# ADC.net
KiCad netlist of a schematic drawn in Altium Designer
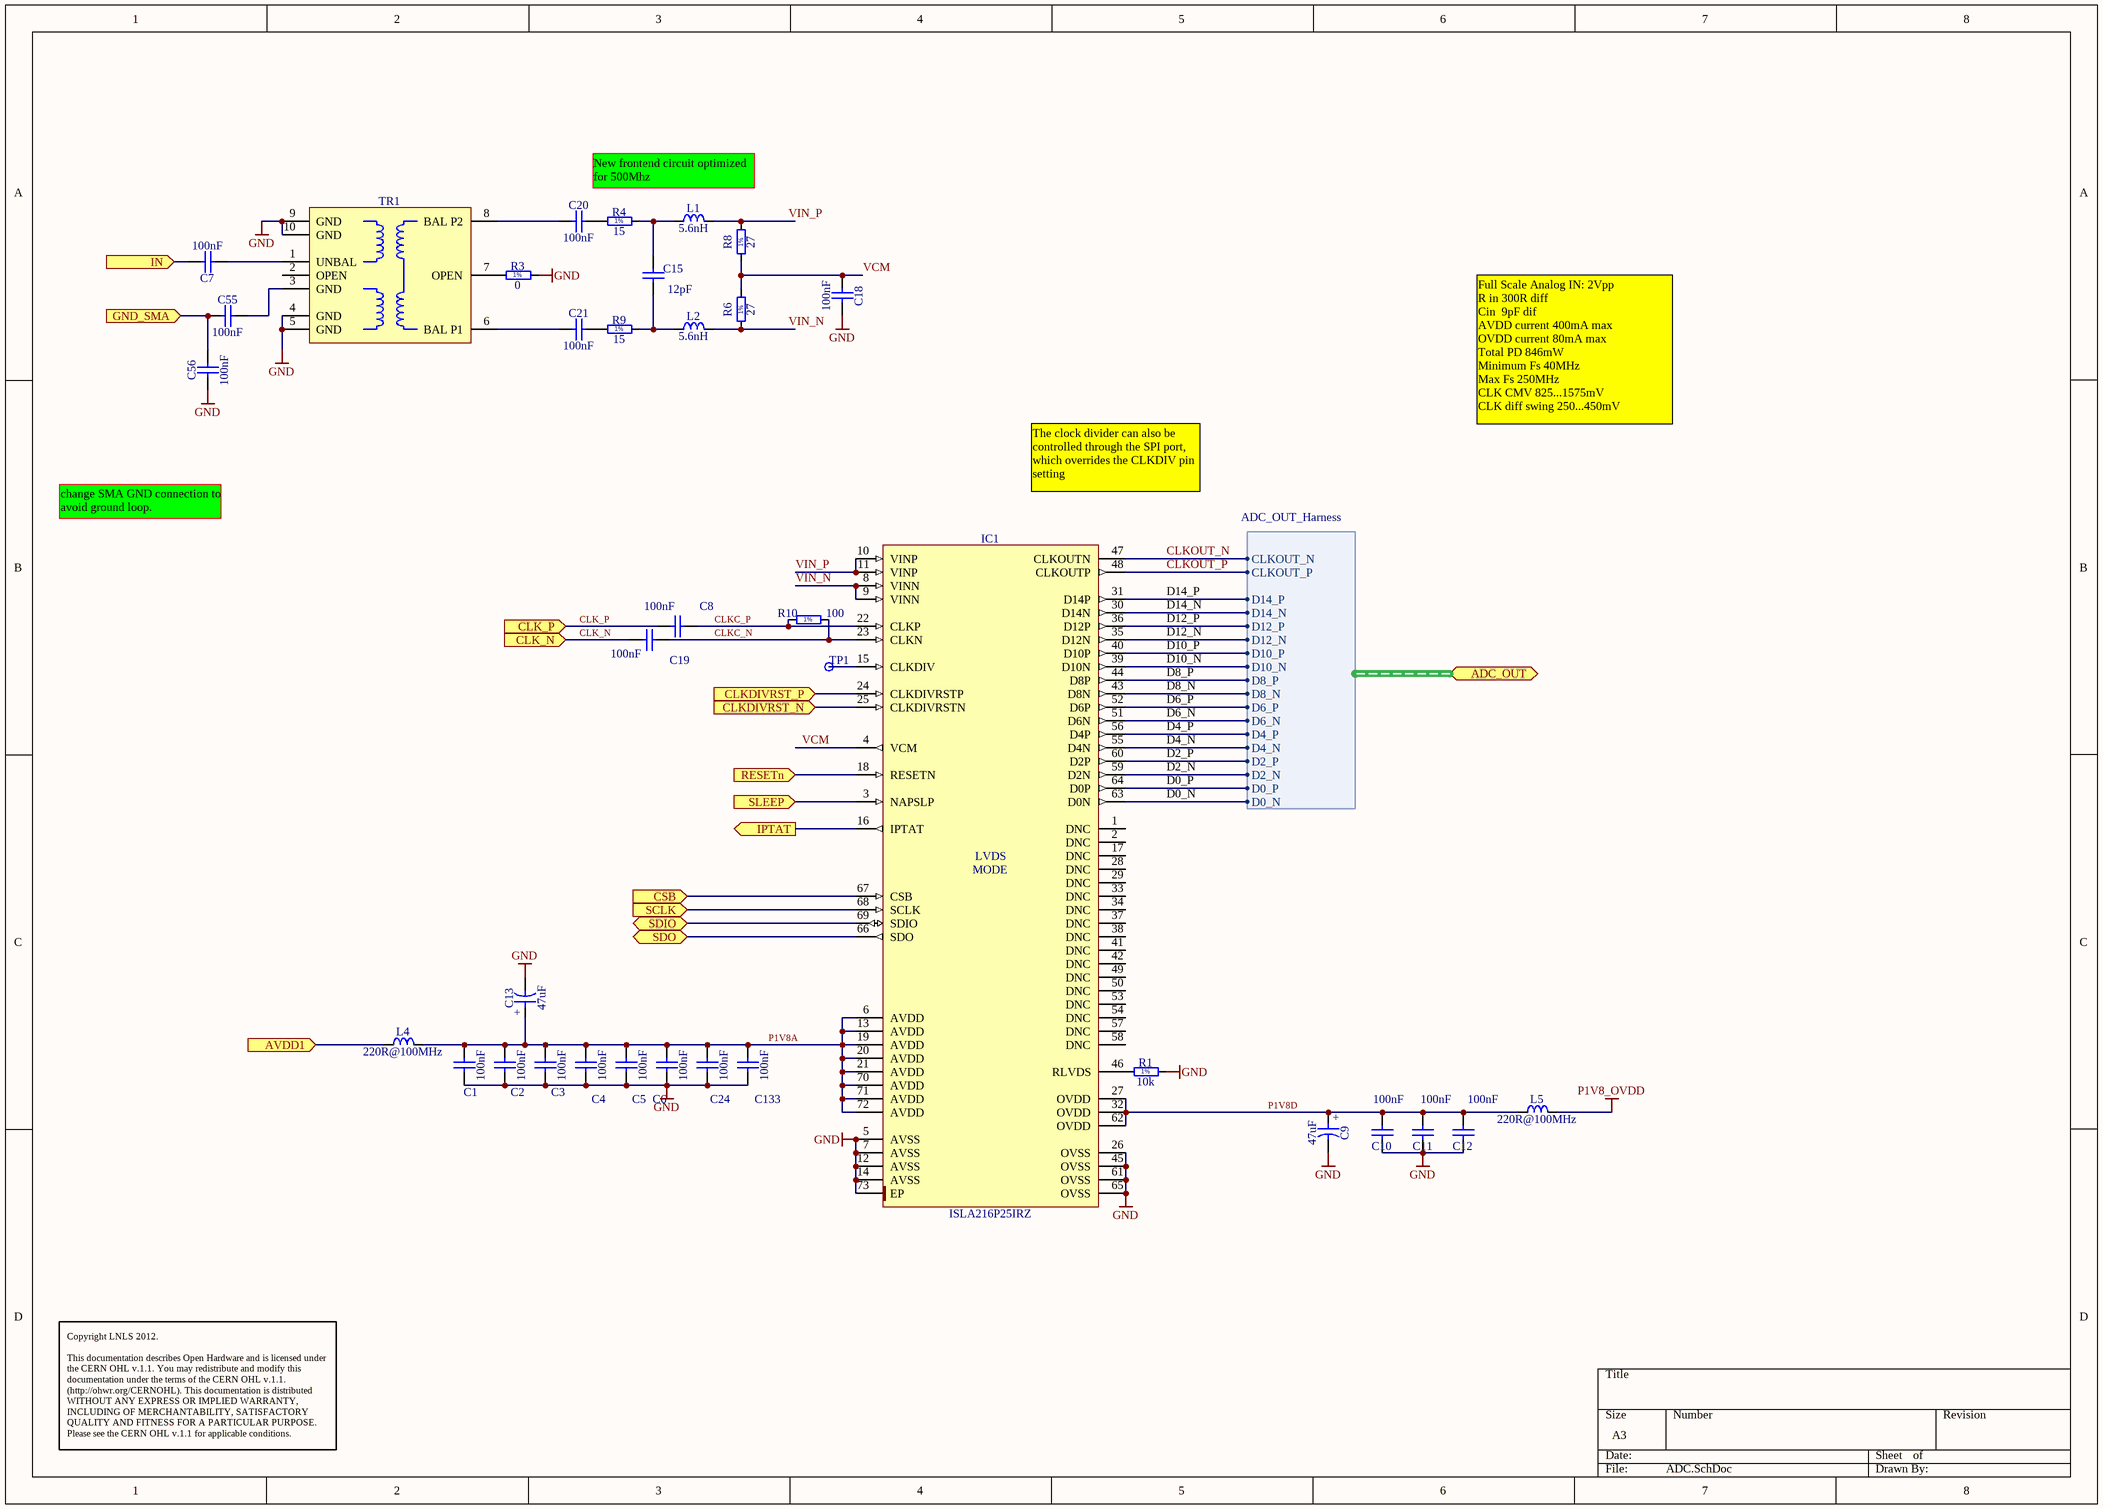
[diagram p0: ADC.SchDoc]

(export (version "E")
  (design (tool "Eeschema 10.0.6"))
  (components
    (comp (ref "C1")
      (value "100nF")
      (footprint "CAPC0603X33N")
      (description "Non-polarised capacitor")
      (fields
        (field (name "PART NUMBER") "CC0201_100NF_6.3V_10%_X5R")
        (field (name "VOLTAGE") "6.3V")
        (field (name "AUTHOR") "CERN DEM JLC")
      )
      (libsource (lib "Capacitors") (part "Capacitor - non polarized"))
    )
    (comp (ref "C2")
      (value "100nF")
      (footprint "CAPC0603X33N")
      (description "Non-polarised capacitor")
      (fields
        (field (name "PART NUMBER") "CC0201_100NF_6.3V_10%_X5R")
        (field (name "VOLTAGE") "6.3V")
        (field (name "AUTHOR") "CERN DEM JLC")
      )
      (libsource (lib "Capacitors") (part "Capacitor - non polarized"))
    )
    (comp (ref "C3")
      (value "100nF")
      (footprint "CAPC0603X33N")
      (description "Non-polarised capacitor")
      (fields
        (field (name "PART NUMBER") "CC0201_100NF_6.3V_10%_X5R")
        (field (name "VOLTAGE") "6.3V")
        (field (name "AUTHOR") "CERN DEM JLC")
      )
      (libsource (lib "Capacitors") (part "Capacitor - non polarized"))
    )
    (comp (ref "C4")
      (value "100nF")
      (footprint "CAPC0603X33N")
      (description "Non-polarised capacitor")
      (fields
        (field (name "PART NUMBER") "CC0201_100NF_6.3V_10%_X5R")
        (field (name "VOLTAGE") "6.3V")
        (field (name "AUTHOR") "CERN DEM JLC")
      )
      (libsource (lib "Capacitors") (part "Capacitor - non polarized"))
    )
    (comp (ref "C5")
      (value "100nF")
      (footprint "CAPC0603X33N")
      (description "Non-polarised capacitor")
      (fields
        (field (name "PART NUMBER") "CC0201_100NF_6.3V_10%_X5R")
        (field (name "VOLTAGE") "6.3V")
        (field (name "AUTHOR") "CERN DEM JLC")
      )
      (libsource (lib "Capacitors") (part "Capacitor - non polarized"))
    )
    (comp (ref "C6")
      (value "100nF")
      (footprint "CAPC0603X33N")
      (description "Non-polarised capacitor")
      (fields
        (field (name "PART NUMBER") "CC0201_100NF_6.3V_10%_X5R")
        (field (name "VOLTAGE") "6.3V")
        (field (name "AUTHOR") "CERN DEM JLC")
      )
      (libsource (lib "Capacitors") (part "Capacitor - non polarized"))
    )
    (comp (ref "C7")
      (value "100nF")
      (footprint "CAPC0603X33N")
      (description "Non-polarised capacitor")
      (fields
        (field (name "PART NUMBER") "CC0201_100NF_6.3V_10%_X5R")
        (field (name "VOLTAGE") "6.3V")
        (field (name "AUTHOR") "CERN DEM JLC")
      )
      (libsource (lib "Capacitors") (part "Capacitor - non polarized"))
    )
    (comp (ref "C8")
      (value "100nF")
      (footprint "CAPC0603X33N")
      (description "Non-polarised capacitor")
      (fields
        (field (name "PART NUMBER") "CC0201_100NF_6.3V_10%_X5R")
        (field (name "VOLTAGE") "6.3V")
        (field (name "AUTHOR") "CERN DEM JLC")
      )
      (libsource (lib "Capacitors") (part "Capacitor - non polarized"))
    )
    (comp (ref "C9")
      (value "47uF")
      (footprint "CAPMP3528X210N")
      (description "Polarised capacitor")
      (fields
        (field (name "PART NUMBER") "CTE3528-21_47UF_6.3V_10%_LESR0250")
        (field (name "VOLTAGE") "6.3V")
        (field (name "AUTHOR") "CERN DEM JLC")
      )
      (libsource (lib "Capacitors") (part "Capacitor - polarized"))
    )
    (comp (ref "C10")
      (value "100nF")
      (footprint "CAPC0603X33N")
      (description "Non-polarised capacitor")
      (fields
        (field (name "PART NUMBER") "CC0201_100NF_6.3V_10%_X5R")
        (field (name "VOLTAGE") "6.3V")
        (field (name "AUTHOR") "CERN DEM JLC")
      )
      (libsource (lib "Capacitors") (part "Capacitor - non polarized"))
    )
    (comp (ref "C11")
      (value "100nF")
      (footprint "CAPC0603X33N")
      (description "Non-polarised capacitor")
      (fields
        (field (name "PART NUMBER") "CC0201_100NF_6.3V_10%_X5R")
        (field (name "VOLTAGE") "6.3V")
        (field (name "AUTHOR") "CERN DEM JLC")
      )
      (libsource (lib "Capacitors") (part "Capacitor - non polarized"))
    )
    (comp (ref "C12")
      (value "100nF")
      (footprint "CAPC0603X33N")
      (description "Non-polarised capacitor")
      (fields
        (field (name "PART NUMBER") "CC0201_100NF_6.3V_10%_X5R")
        (field (name "VOLTAGE") "6.3V")
        (field (name "AUTHOR") "CERN DEM JLC")
      )
      (libsource (lib "Capacitors") (part "Capacitor - non polarized"))
    )
    (comp (ref "C13")
      (value "47uF")
      (footprint "CAPMP3528X210N")
      (description "Polarised capacitor")
      (fields
        (field (name "PART NUMBER") "CTE3528-21_47UF_6.3V_10%_LESR0250")
        (field (name "VOLTAGE") "6.3V")
        (field (name "AUTHOR") "CERN DEM JLC")
      )
      (libsource (lib "Capacitors") (part "Capacitor - polarized"))
    )
    (comp (ref "C15")
      (value "12pF")
      (footprint "CAPC2012X135N")
      (description "Non-polarised capacitor")
      (fields
        (field (name "PART NUMBER") "CC0805_12PF_50V_5%_NP0")
        (field (name "VOLTAGE") "50V")
        (field (name "AUTHOR") "CERN DEM JLC")
      )
      (libsource (lib "Capacitors") (part "Capacitor - non polarized"))
    )
    (comp (ref "C18")
      (value "100nF")
      (footprint "CAPC0603X33N")
      (description "Non-polarised capacitor")
      (fields
        (field (name "PART NUMBER") "CC0201_100NF_6.3V_10%_X5R")
        (field (name "VOLTAGE") "6.3V")
        (field (name "AUTHOR") "CERN DEM JLC")
      )
      (libsource (lib "Capacitors") (part "Capacitor - non polarized"))
    )
    (comp (ref "C19")
      (value "100nF")
      (footprint "CAPC0603X33N")
      (description "Non-polarised capacitor")
      (fields
        (field (name "PART NUMBER") "CC0201_100NF_6.3V_10%_X5R")
        (field (name "VOLTAGE") "6.3V")
        (field (name "AUTHOR") "CERN DEM JLC")
      )
      (libsource (lib "Capacitors") (part "Capacitor - non polarized"))
    )
    (comp (ref "C20")
      (value "100nF")
      (footprint "CAPC0603X33N")
      (description "Non-polarised capacitor")
      (fields
        (field (name "PART NUMBER") "CC0201_100NF_6.3V_10%_X5R")
        (field (name "VOLTAGE") "6.3V")
        (field (name "AUTHOR") "CERN DEM JLC")
      )
      (libsource (lib "Capacitors") (part "Capacitor - non polarized"))
    )
    (comp (ref "C21")
      (value "100nF")
      (footprint "CAPC0603X33N")
      (description "Non-polarised capacitor")
      (fields
        (field (name "PART NUMBER") "CC0201_100NF_6.3V_10%_X5R")
        (field (name "VOLTAGE") "6.3V")
        (field (name "AUTHOR") "CERN DEM JLC")
      )
      (libsource (lib "Capacitors") (part "Capacitor - non polarized"))
    )
    (comp (ref "C24")
      (value "100nF")
      (footprint "CAPC0603X33N")
      (description "Non-polarised capacitor")
      (fields
        (field (name "PART NUMBER") "CC0201_100NF_6.3V_10%_X5R")
        (field (name "VOLTAGE") "6.3V")
        (field (name "AUTHOR") "CERN DEM JLC")
      )
      (libsource (lib "Capacitors") (part "Capacitor - non polarized"))
    )
    (comp (ref "C55")
      (value "100nF")
      (footprint "CAPC0603X33N")
      (description "Non-polarised capacitor")
      (fields
        (field (name "PART NUMBER") "CC0201_100NF_6.3V_10%_X5R")
        (field (name "VOLTAGE") "6.3V")
        (field (name "AUTHOR") "CERN DEM JLC")
      )
      (libsource (lib "Capacitors") (part "Capacitor - non polarized"))
    )
    (comp (ref "C56")
      (value "100nF")
      (footprint "CAPC0603X33N")
      (description "Non-polarised capacitor")
      (fields
        (field (name "PART NUMBER") "CC0201_100NF_6.3V_10%_X5R")
        (field (name "VOLTAGE") "6.3V")
        (field (name "AUTHOR") "CERN DEM JLC")
      )
      (libsource (lib "Capacitors") (part "Capacitor - non polarized"))
    )
    (comp (ref "C133")
      (value "100nF")
      (footprint "CAPC0603X33N")
      (description "Non-polarised capacitor")
      (fields
        (field (name "PART NUMBER") "CC0201_100NF_6.3V_10%_X5R")
        (field (name "VOLTAGE") "6.3V")
        (field (name "AUTHOR") "CERN DEM JLC")
      )
      (libsource (lib "Capacitors") (part "Capacitor - non polarized"))
    )
    (comp (ref "IC1")
      (value "ISLA216P25IRZ")
      (footprint "INTERSIL_L72.10x10E")
      (description "16-Bit, 250MSPS ADC (LVDS Mode)")
      (fields (field (name "MANUFACTURER") "INTERSIL") (field (name "AUTHOR") "CERN DEM JLC"))
      (libsource (lib "ICs And Semiconductors") (part "ISLA216P25IRZ_LVDS"))
    )
    (comp (ref "L1")
      (value "5.6nH")
      (footprint "INDC1005X55N")
      (description "Inductor")
      (fields
        (field (name "PART NUMBER") "IND0402_5.6nH_0.3n_JOHANSON_L-07C5N6SV6T")
        (field (name "POWER") "300mA")
        (field (name "AUTHOR") "LNLS DIG GBMB")
      )
      (libsource (lib "Inductors & Transformers") (part "Inductor"))
    )
    (comp (ref "L2")
      (value "5.6nH")
      (footprint "INDC1005X55N")
      (description "Inductor")
      (fields
        (field (name "PART NUMBER") "IND0402_5.6nH_0.3n_JOHANSON_L-07C5N6SV6T")
        (field (name "POWER") "300mA")
        (field (name "AUTHOR") "LNLS DIG GBMB")
      )
      (libsource (lib "Inductors & Transformers") (part "Inductor"))
    )
    (comp (ref "L4")
      (value "220R@100MHz")
      (footprint "INDC2012X105N")
      (description "Inductor")
      (fields
        (field (name "PART NUMBER") "IND0805_MURATA_BLM21PG221SN1D")
        (field (name "POWER") "2A")
        (field (name "AUTHOR") "CERN DEM JLC")
      )
      (libsource (lib "Inductors & Transformers") (part "Inductor"))
    )
    (comp (ref "L5")
      (value "220R@100MHz")
      (footprint "INDC2012X105N")
      (description "Inductor")
      (fields
        (field (name "PART NUMBER") "IND0805_MURATA_BLM21PG221SN1D")
        (field (name "POWER") "2A")
        (field (name "AUTHOR") "CERN DEM JLC")
      )
      (libsource (lib "Inductors & Transformers") (part "Inductor"))
    )
    (comp (ref "R1")
      (value "10k")
      (footprint "RESC1005X40N")
      (description "Resistor - 1%")
      (fields
        (field (name "PART NUMBER") "R0402_10K_1%_0.0625W_100PPM")
        (field (name "POWER") "0.0625W")
        (field (name "AUTHOR") "CERN DEM JLC")
      )
      (libsource (lib "Resistors") (part "Resistor - 1%"))
    )
    (comp (ref "R3")
      (value "0")
      (footprint "RESC1005X40N")
      (description "Resistor - 1%")
      (fields
        (field (name "PART NUMBER") "R0402_0R_JUMPER")
        (field (name "MANUFACTURER") "GENERIC")
        (field (name "AUTHOR") "CERN DEM JLC")
      )
      (libsource (lib "Resistors") (part "Resistor - 1%"))
    )
    (comp (ref "R4")
      (value "15")
      (footprint "RESC1005X40N")
      (description "Resistor - 1%")
      (fields
        (field (name "PART NUMBER") "CRCW04026R98FKED")
        (field (name "POWER") "0.0625W")
        (field (name "AUTHOR") "CERN DEM JLC")
      )
      (libsource (lib "Resistors") (part "Resistor - 1%"))
    )
    (comp (ref "R6")
      (value "27")
      (footprint "RESC1005X40N")
      (description "Resistor - 1%")
      (fields
        (field (name "PART NUMBER") "RC0402FR-0720RL")
        (field (name "POWER") "0.0625W")
        (field (name "AUTHOR") "CERN DEM JLC")
      )
      (libsource (lib "Resistors") (part "Resistor - 1%"))
    )
    (comp (ref "R8")
      (value "27")
      (footprint "RESC1005X40N")
      (description "Resistor - 1%")
      (fields
        (field (name "PART NUMBER") "RC0402FR-0720RL")
        (field (name "POWER") "0.0625W")
        (field (name "AUTHOR") "CERN DEM JLC")
      )
      (libsource (lib "Resistors") (part "Resistor - 1%"))
    )
    (comp (ref "R9")
      (value "15")
      (footprint "RESC1005X40N")
      (description "Resistor - 1%")
      (fields
        (field (name "PART NUMBER") "CRCW04026R98FKED")
        (field (name "POWER") "0.0625W")
        (field (name "AUTHOR") "CERN DEM JLC")
      )
      (libsource (lib "Resistors") (part "Resistor - 1%"))
    )
    (comp (ref "R10")
      (value "100")
      (footprint "RESC1005X40N")
      (description "Resistor - 1%")
      (fields
        (field (name "PART NUMBER") "R0402_100R_1%_0.0625W_100PPM")
        (field (name "POWER") "0.0625W")
        (field (name "AUTHOR") "CERN DEM JLC")
      )
      (libsource (lib "Resistors") (part "Resistor - 1%"))
    )
    (comp (ref "TP1")
      (value "~")
      (footprint "TPR120")
      (description "Test Point")
      (fields (field (name "PART NUMBER") "SMD_PAD_1.20_d_MM") (field (name "AUTHOR") "LNLS DIG GBMB"))
      (libsource (lib "Eletro-mechanical") (part "Test Point"))
    )
    (comp (ref "TR1")
      (value "~")
      (footprint "XFMR_ANAREN_BD0205F5050A00")
      (description "70MHz - 1000MHz Ultra Low Profile Sub-Miniature Balanced to Unbalanced Transformer")
      (fields
        (field (name "PART NUMBER") "XFMR_ANAREN_BD0205F5050A00")
        (field (name "MANUFACTURER") "ANAREN")
        (field (name "AUTHOR") "CERN DEM JLC")
      )
      (libsource (lib "Inductors & Transformers") (part "XFMR_ANAREN_BD0205F5050A00"))
    )
  )
  (nets
    (net (code "2") (name "/AVDD1") (class "Default")
      (node (ref "L4") (pin "1") (pinfunction "1_1") (pintype "passive"))
    )
    (net (code "3") (name "/CLKC_N") (class "Default")
      (node (ref "C19") (pin "2") (pinfunction "2_2") (pintype "passive"))
      (node (ref "IC1") (pin "23") (pinfunction "CLKN_23") (pintype "input"))
      (node (ref "R10") (pin "2") (pinfunction "2_2") (pintype "passive"))
    )
    (net (code "4") (name "/CLKC_P") (class "Default")
      (node (ref "C8") (pin "2") (pinfunction "2_2") (pintype "passive"))
      (node (ref "IC1") (pin "22") (pinfunction "CLKP_22") (pintype "input"))
      (node (ref "R10") (pin "1") (pinfunction "1_1") (pintype "passive"))
    )
    (net (code "5") (name "/CLKDIVRST_N") (class "Default")
      (node (ref "IC1") (pin "25") (pinfunction "CLKDIVRSTN_25") (pintype "input"))
    )
    (net (code "6") (name "/CLKDIVRST_P") (class "Default")
      (node (ref "IC1") (pin "24") (pinfunction "CLKDIVRSTP_24") (pintype "input"))
    )
    (net (code "7") (name "/CLKOUT_N") (class "Default")
      (node (ref "IC1") (pin "47") (pinfunction "CLKOUTN_47") (pintype "open_collector"))
    )
    (net (code "8") (name "/CLKOUT_P") (class "Default")
      (node (ref "IC1") (pin "48") (pinfunction "CLKOUTP_48") (pintype "output"))
    )
    (net (code "9") (name "/CLK_N") (class "Default")
      (node (ref "C19") (pin "1") (pinfunction "1_1") (pintype "passive"))
    )
    (net (code "10") (name "/CLK_P") (class "Default")
      (node (ref "C8") (pin "1") (pinfunction "1_1") (pintype "passive"))
    )
    (net (code "11") (name "/CSB") (class "Default")
      (node (ref "IC1") (pin "67") (pinfunction "CSB_67") (pintype "input"))
    )
    (net (code "12") (name "/D0_N") (class "Default")
      (node (ref "IC1") (pin "63") (pinfunction "D0N_63") (pintype "output"))
    )
    (net (code "13") (name "/D0_P") (class "Default")
      (node (ref "IC1") (pin "64") (pinfunction "D0P_64") (pintype "output"))
    )
    (net (code "14") (name "/D2_N") (class "Default")
      (node (ref "IC1") (pin "59") (pinfunction "D2N_59") (pintype "output"))
    )
    (net (code "15") (name "/D2_P") (class "Default")
      (node (ref "IC1") (pin "60") (pinfunction "D2P_60") (pintype "output"))
    )
    (net (code "16") (name "/D4_N") (class "Default")
      (node (ref "IC1") (pin "55") (pinfunction "D4N_55") (pintype "output"))
    )
    (net (code "17") (name "/D4_P") (class "Default")
      (node (ref "IC1") (pin "56") (pinfunction "D4P_56") (pintype "output"))
    )
    (net (code "18") (name "/D6_N") (class "Default")
      (node (ref "IC1") (pin "51") (pinfunction "D6N_51") (pintype "output"))
    )
    (net (code "19") (name "/D6_P") (class "Default")
      (node (ref "IC1") (pin "52") (pinfunction "D6P_52") (pintype "output"))
    )
    (net (code "20") (name "/D8_N") (class "Default")
      (node (ref "IC1") (pin "43") (pinfunction "D8N_43") (pintype "output"))
    )
    (net (code "21") (name "/D8_P") (class "Default")
      (node (ref "IC1") (pin "44") (pinfunction "D8P_44") (pintype "output"))
    )
    (net (code "22") (name "/D10_N") (class "Default")
      (node (ref "IC1") (pin "39") (pinfunction "D10N_39") (pintype "output"))
    )
    (net (code "23") (name "/D10_P") (class "Default")
      (node (ref "IC1") (pin "40") (pinfunction "D10P_40") (pintype "output"))
    )
    (net (code "24") (name "/D12_N") (class "Default")
      (node (ref "IC1") (pin "35") (pinfunction "D12N_35") (pintype "output"))
    )
    (net (code "25") (name "/D12_P") (class "Default")
      (node (ref "IC1") (pin "36") (pinfunction "D12P_36") (pintype "output"))
    )
    (net (code "26") (name "/D14_N") (class "Default")
      (node (ref "IC1") (pin "30") (pinfunction "D14N_30") (pintype "output"))
    )
    (net (code "27") (name "/D14_P") (class "Default")
      (node (ref "IC1") (pin "31") (pinfunction "D14P_31") (pintype "output"))
    )
    (net (code "28") (name "/GND_SMA") (class "Default")
      (node (ref "C55") (pin "1") (pinfunction "1_1") (pintype "passive"))
      (node (ref "C56") (pin "2") (pinfunction "2_2") (pintype "passive"))
    )
    (net (code "29") (name "/IN") (class "Default")
      (node (ref "C7") (pin "2") (pinfunction "2_2") (pintype "passive"))
    )
    (net (code "30") (name "/IPTAT") (class "Default")
      (node (ref "IC1") (pin "16") (pinfunction "IPTAT_16") (pintype "output"))
    )
    (net (code "31") (name "/P1V8A") (class "Default")
      (node (ref "C1") (pin "2") (pinfunction "2_2") (pintype "passive"))
      (node (ref "C13") (pin "1") (pinfunction "1_1") (pintype "passive"))
      (node (ref "C133") (pin "2") (pinfunction "2_2") (pintype "passive"))
      (node (ref "C2") (pin "2") (pinfunction "2_2") (pintype "passive"))
      (node (ref "C24") (pin "2") (pinfunction "2_2") (pintype "passive"))
      (node (ref "C3") (pin "2") (pinfunction "2_2") (pintype "passive"))
      (node (ref "C4") (pin "2") (pinfunction "2_2") (pintype "passive"))
      (node (ref "C5") (pin "2") (pinfunction "2_2") (pintype "passive"))
      (node (ref "C6") (pin "2") (pinfunction "2_2") (pintype "passive"))
      (node (ref "IC1") (pin "13") (pinfunction "AVDD_13") (pintype "power_in"))
      (node (ref "IC1") (pin "19") (pinfunction "AVDD_19") (pintype "power_in"))
      (node (ref "IC1") (pin "20") (pinfunction "AVDD_20") (pintype "power_in"))
      (node (ref "IC1") (pin "21") (pinfunction "AVDD_21") (pintype "power_in"))
      (node (ref "IC1") (pin "6") (pinfunction "AVDD_6") (pintype "power_in"))
      (node (ref "IC1") (pin "70") (pinfunction "AVDD_70") (pintype "power_in"))
      (node (ref "IC1") (pin "71") (pinfunction "AVDD_71") (pintype "power_in"))
      (node (ref "IC1") (pin "72") (pinfunction "AVDD_72") (pintype "power_in"))
      (node (ref "L4") (pin "2") (pinfunction "2_2") (pintype "passive"))
    )
    (net (code "32") (name "/P1V8D") (class "Default")
      (node (ref "C10") (pin "2") (pinfunction "2_2") (pintype "passive"))
      (node (ref "C11") (pin "2") (pinfunction "2_2") (pintype "passive"))
      (node (ref "C12") (pin "2") (pinfunction "2_2") (pintype "passive"))
      (node (ref "C9") (pin "1") (pinfunction "1_1") (pintype "passive"))
      (node (ref "IC1") (pin "27") (pinfunction "OVDD_27") (pintype "power_in"))
      (node (ref "IC1") (pin "32") (pinfunction "OVDD_32") (pintype "power_in"))
      (node (ref "IC1") (pin "62") (pinfunction "OVDD_62") (pintype "power_in"))
      (node (ref "L5") (pin "1") (pinfunction "1_1") (pintype "passive"))
    )
    (net (code "33") (name "/RESETn") (class "Default")
      (node (ref "IC1") (pin "18") (pinfunction "RESETN_18") (pintype "input"))
    )
    (net (code "34") (name "/SCLK") (class "Default")
      (node (ref "IC1") (pin "68") (pinfunction "SCLK_68") (pintype "input"))
    )
    (net (code "35") (name "/SDIO") (class "Default")
      (node (ref "IC1") (pin "69") (pinfunction "SDIO_69") (pintype "bidirectional"))
    )
    (net (code "36") (name "/SDO") (class "Default")
      (node (ref "IC1") (pin "66") (pinfunction "SDO_66") (pintype "output"))
    )
    (net (code "37") (name "/SLEEP") (class "Default")
      (node (ref "IC1") (pin "3") (pinfunction "NAPSLP_3") (pintype "input"))
    )
    (net (code "38") (name "/VCM") (class "Default")
      (node (ref "C18") (pin "1") (pinfunction "1_1") (pintype "passive"))
      (node (ref "IC1") (pin "4") (pinfunction "VCM_4") (pintype "output"))
      (node (ref "R6") (pin "2") (pinfunction "2_2") (pintype "passive"))
      (node (ref "R8") (pin "1") (pinfunction "1_1") (pintype "passive"))
    )
    (net (code "39") (name "/VIN_N") (class "Default")
      (node (ref "IC1") (pin "8") (pinfunction "VINN_8") (pintype "input"))
      (node (ref "IC1") (pin "9") (pinfunction "VINN_9") (pintype "input"))
      (node (ref "L2") (pin "2") (pinfunction "2_2") (pintype "passive"))
      (node (ref "R6") (pin "1") (pinfunction "1_1") (pintype "passive"))
    )
    (net (code "40") (name "/VIN_P") (class "Default")
      (node (ref "IC1") (pin "10") (pinfunction "VINP_10") (pintype "input"))
      (node (ref "IC1") (pin "11") (pinfunction "VINP_11") (pintype "input"))
      (node (ref "L1") (pin "2") (pinfunction "2_2") (pintype "passive"))
      (node (ref "R8") (pin "2") (pinfunction "2_2") (pintype "passive"))
    )
    (net (code "42") (name "GND") (class "Default")
      (node (ref "C1") (pin "1") (pinfunction "1_1") (pintype "passive"))
      (node (ref "C10") (pin "1") (pinfunction "1_1") (pintype "passive"))
      (node (ref "C11") (pin "1") (pinfunction "1_1") (pintype "passive"))
      (node (ref "C12") (pin "1") (pinfunction "1_1") (pintype "passive"))
      (node (ref "C13") (pin "2") (pinfunction "2_2") (pintype "passive"))
      (node (ref "C133") (pin "1") (pinfunction "1_1") (pintype "passive"))
      (node (ref "C18") (pin "2") (pinfunction "2_2") (pintype "passive"))
      (node (ref "C2") (pin "1") (pinfunction "1_1") (pintype "passive"))
      (node (ref "C24") (pin "1") (pinfunction "1_1") (pintype "passive"))
      (node (ref "C3") (pin "1") (pinfunction "1_1") (pintype "passive"))
      (node (ref "C4") (pin "1") (pinfunction "1_1") (pintype "passive"))
      (node (ref "C5") (pin "1") (pinfunction "1_1") (pintype "passive"))
      (node (ref "C56") (pin "1") (pinfunction "1_1") (pintype "passive"))
      (node (ref "C6") (pin "1") (pinfunction "1_1") (pintype "passive"))
      (node (ref "C9") (pin "2") (pinfunction "2_2") (pintype "passive"))
      (node (ref "IC1") (pin "12") (pinfunction "AVSS_12") (pintype "power_in"))
      (node (ref "IC1") (pin "14") (pinfunction "AVSS_14") (pintype "power_in"))
      (node (ref "IC1") (pin "26") (pinfunction "OVSS_26") (pintype "power_in"))
      (node (ref "IC1") (pin "45") (pinfunction "OVSS_45") (pintype "power_in"))
      (node (ref "IC1") (pin "5") (pinfunction "AVSS_5") (pintype "power_in"))
      (node (ref "IC1") (pin "61") (pinfunction "OVSS_61") (pintype "power_in"))
      (node (ref "IC1") (pin "65") (pinfunction "OVSS_65") (pintype "power_in"))
      (node (ref "IC1") (pin "7") (pinfunction "AVSS_7") (pintype "power_in"))
      (node (ref "IC1") (pin "73") (pinfunction "EP_73") (pintype "power_in"))
      (node (ref "R1") (pin "2") (pinfunction "2_2") (pintype "passive"))
      (node (ref "R3") (pin "2") (pinfunction "2_2") (pintype "passive"))
      (node (ref "TR1") (pin "10") (pinfunction "GND_10") (pintype "power_in"))
      (node (ref "TR1") (pin "4") (pinfunction "GND_4") (pintype "power_in"))
      (node (ref "TR1") (pin "5") (pinfunction "GND_5") (pintype "power_in"))
      (node (ref "TR1") (pin "9") (pinfunction "GND_9") (pintype "power_in"))
    )
    (net (code "43") (name "Net-(C15-Pad1)") (class "Default")
      (node (ref "C15") (pin "1") (pinfunction "1_1") (pintype "passive"))
      (node (ref "L2") (pin "1") (pinfunction "1_1") (pintype "passive"))
      (node (ref "R9") (pin "2") (pinfunction "2_2") (pintype "passive"))
    )
    (net (code "44") (name "Net-(C15-Pad2)") (class "Default")
      (node (ref "C15") (pin "2") (pinfunction "2_2") (pintype "passive"))
      (node (ref "L1") (pin "1") (pinfunction "1_1") (pintype "passive"))
      (node (ref "R4") (pin "2") (pinfunction "2_2") (pintype "passive"))
    )
    (net (code "45") (name "Net-(C20-Pad2)") (class "Default")
      (node (ref "C20") (pin "2") (pinfunction "2_2") (pintype "passive"))
      (node (ref "R4") (pin "1") (pinfunction "1_1") (pintype "passive"))
    )
    (net (code "46") (name "Net-(C21-Pad2)") (class "Default")
      (node (ref "C21") (pin "2") (pinfunction "2_2") (pintype "passive"))
      (node (ref "R9") (pin "1") (pinfunction "1_1") (pintype "passive"))
    )
    (net (code "47") (name "Net-(C55-Pad2)") (class "Default")
      (node (ref "C55") (pin "2") (pinfunction "2_2") (pintype "passive"))
      (node (ref "TR1") (pin "3") (pinfunction "GND_3") (pintype "power_in"))
    )
    (net (code "48") (name "Net-(IC1-CLKDIV)") (class "Default")
      (node (ref "IC1") (pin "15") (pinfunction "CLKDIV_15") (pintype "input"))
      (node (ref "TP1") (pin "1") (pinfunction "1_1") (pintype "bidirectional"))
    )
    (net (code "49") (name "Net-(IC1-RLVDS)") (class "Default")
      (node (ref "IC1") (pin "46") (pinfunction "RLVDS_46") (pintype "passive"))
      (node (ref "R1") (pin "1") (pinfunction "1_1") (pintype "passive"))
    )
    (net (code "50") (name "Net-(R3-Pad1)") (class "Default")
      (node (ref "R3") (pin "1") (pinfunction "1_1") (pintype "passive"))
      (node (ref "TR1") (pin "7") (pinfunction "OPEN_7") (pintype "passive"))
    )
    (net (code "51") (name "Net-(TR1-BAL_P1)") (class "Default")
      (node (ref "C21") (pin "1") (pinfunction "1_1") (pintype "passive"))
      (node (ref "TR1") (pin "6") (pinfunction "BAL_P1_6") (pintype "passive"))
    )
    (net (code "52") (name "Net-(TR1-BAL_P2)") (class "Default")
      (node (ref "C20") (pin "1") (pinfunction "1_1") (pintype "passive"))
      (node (ref "TR1") (pin "8") (pinfunction "BAL_P2_8") (pintype "passive"))
    )
    (net (code "53") (name "Net-(TR1-UNBAL)") (class "Default")
      (node (ref "C7") (pin "1") (pinfunction "1_1") (pintype "passive"))
      (node (ref "TR1") (pin "1") (pinfunction "UNBAL_1") (pintype "passive"))
    )
    (net (code "54") (name "P1V8_OVDD") (class "Default")
      (node (ref "L5") (pin "2") (pinfunction "2_2") (pintype "passive"))
    )
    (net (code "55") (name "unconnected-(IC1-DNC-Pad1)") (class "Default")
      (node (ref "IC1") (pin "1") (pinfunction "DNC_1") (pintype "passive"))
    )
    (net (code "56") (name "unconnected-(IC1-DNC-Pad2)") (class "Default")
      (node (ref "IC1") (pin "2") (pinfunction "DNC_2") (pintype "passive"))
    )
    (net (code "57") (name "unconnected-(IC1-DNC-Pad17)") (class "Default")
      (node (ref "IC1") (pin "17") (pinfunction "DNC_17") (pintype "passive"))
    )
    (net (code "58") (name "unconnected-(IC1-DNC-Pad28)") (class "Default")
      (node (ref "IC1") (pin "28") (pinfunction "DNC_28") (pintype "passive"))
    )
    (net (code "59") (name "unconnected-(IC1-DNC-Pad29)") (class "Default")
      (node (ref "IC1") (pin "29") (pinfunction "DNC_29") (pintype "passive"))
    )
    (net (code "60") (name "unconnected-(IC1-DNC-Pad33)") (class "Default")
      (node (ref "IC1") (pin "33") (pinfunction "DNC_33") (pintype "passive"))
    )
    (net (code "61") (name "unconnected-(IC1-DNC-Pad34)") (class "Default")
      (node (ref "IC1") (pin "34") (pinfunction "DNC_34") (pintype "passive"))
    )
    (net (code "62") (name "unconnected-(IC1-DNC-Pad37)") (class "Default")
      (node (ref "IC1") (pin "37") (pinfunction "DNC_37") (pintype "passive"))
    )
    (net (code "63") (name "unconnected-(IC1-DNC-Pad38)") (class "Default")
      (node (ref "IC1") (pin "38") (pinfunction "DNC_38") (pintype "passive"))
    )
    (net (code "64") (name "unconnected-(IC1-DNC-Pad41)") (class "Default")
      (node (ref "IC1") (pin "41") (pinfunction "DNC_41") (pintype "passive"))
    )
    (net (code "65") (name "unconnected-(IC1-DNC-Pad42)") (class "Default")
      (node (ref "IC1") (pin "42") (pinfunction "DNC_42") (pintype "passive"))
    )
    (net (code "66") (name "unconnected-(IC1-DNC-Pad49)") (class "Default")
      (node (ref "IC1") (pin "49") (pinfunction "DNC_49") (pintype "passive"))
    )
    (net (code "67") (name "unconnected-(IC1-DNC-Pad50)") (class "Default")
      (node (ref "IC1") (pin "50") (pinfunction "DNC_50") (pintype "passive"))
    )
    (net (code "68") (name "unconnected-(IC1-DNC-Pad53)") (class "Default")
      (node (ref "IC1") (pin "53") (pinfunction "DNC_53") (pintype "passive"))
    )
    (net (code "69") (name "unconnected-(IC1-DNC-Pad54)") (class "Default")
      (node (ref "IC1") (pin "54") (pinfunction "DNC_54") (pintype "passive"))
    )
    (net (code "70") (name "unconnected-(IC1-DNC-Pad57)") (class "Default")
      (node (ref "IC1") (pin "57") (pinfunction "DNC_57") (pintype "passive"))
    )
    (net (code "71") (name "unconnected-(IC1-DNC-Pad58)") (class "Default")
      (node (ref "IC1") (pin "58") (pinfunction "DNC_58") (pintype "passive"))
    )
    (net (code "72") (name "unconnected-(TR1-OPEN-Pad2)") (class "Default")
      (node (ref "TR1") (pin "2") (pinfunction "OPEN_2") (pintype "passive"))
    )
  )
)
